# Project_PCBTA.net
KiCad netlist of a schematic drawn in Altium Designer
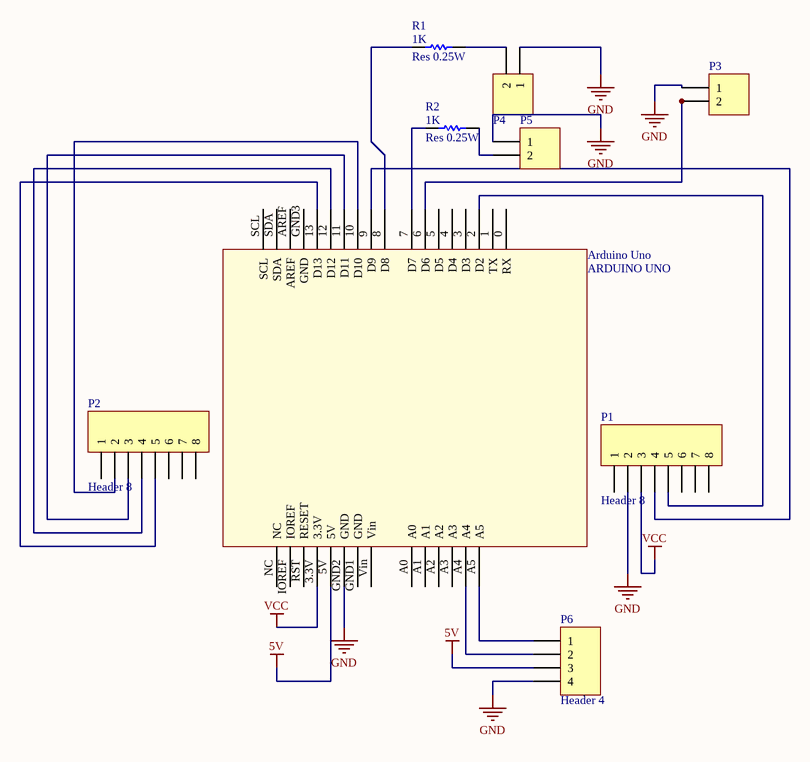
[diagram p0: Project_PCBTA.SchDoc]

(export (version "E")
  (design (tool "Eeschema 10.0.6"))
  (components
    (comp (ref "Arduino Uno")
      (value "ARDUINO UNO")
      (footprint "ARDUINO UNO")
      (libsource (lib "Arduino") (part "ARDUINO UNO"))
    )
    (comp (ref "P1")
      (value "Header 8")
      (footprint "HDR1X8")
      (description "Header, 8-Pin")
      (fields (field (name "PUBLISHER") "Altium Limited"))
      (libsource (lib "Miscellaneous Connectors") (part "Header 8"))
    )
    (comp (ref "P2")
      (value "Header 8")
      (footprint "HDR1X8")
      (description "Header, 8-Pin")
      (fields (field (name "PUBLISHER") "Altium Limited"))
      (libsource (lib "Miscellaneous Connectors") (part "Header 8"))
    )
    (comp (ref "P3")
      (value "Header 2")
      (footprint "My_1X02")
      (description "Header, 2-Pin")
      (fields (field (name "PUBLISHER") "Altium Limited"))
      (libsource (lib "Mylib") (part "Header 2"))
    )
    (comp (ref "P4")
      (value "Header 2")
      (footprint "My_1X02")
      (description "Header, 2-Pin")
      (fields (field (name "PUBLISHER") "Altium Limited"))
      (libsource (lib "") (part "Header 2_1"))
    )
    (comp (ref "P5")
      (value "Header 2")
      (footprint "My_1X02")
      (description "Header, 2-Pin")
      (fields (field (name "PUBLISHER") "Altium Limited"))
      (libsource (lib "Mylib") (part "Header 2"))
    )
    (comp (ref "P6")
      (value "Header 4")
      (footprint "HDR1X4")
      (description "Header, 4-Pin")
      (fields (field (name "PUBLISHER") "Altium Limited"))
      (libsource (lib "Miscellaneous Connectors") (part "Header 4"))
    )
    (comp (ref "R1")
      (value "Res 0.25W")
      (footprint "Res 0.25")
      (libsource (lib "Error15 Library REV") (part "Res 0.25W"))
    )
    (comp (ref "R2")
      (value "Res 0.25W")
      (footprint "Res 0.25")
      (libsource (lib "Error15 Library REV") (part "Res 0.25W"))
    )
  )
  (nets
    (net (code "1") (name "5V") (class "Default")
      (node (ref "Arduino Uno") (pin "5V") (pinfunction "5V_5V") (pintype "passive"))
      (node (ref "P6") (pin "3") (pinfunction "3_3") (pintype "passive"))
    )
    (net (code "2") (name "GND") (class "Default")
      (node (ref "Arduino Uno") (pin "GND2") (pinfunction "GND_GND2") (pintype "passive"))
      (node (ref "P1") (pin "2") (pinfunction "2_2") (pintype "passive"))
      (node (ref "P3") (pin "1") (pinfunction "1_1") (pintype "passive"))
      (node (ref "P4") (pin "1") (pinfunction "1_1") (pintype "passive"))
      (node (ref "P5") (pin "1") (pinfunction "1_1") (pintype "passive"))
      (node (ref "P6") (pin "4") (pinfunction "4_4") (pintype "passive"))
    )
    (net (code "3") (name "Net-(Arduino Uno-D2)") (class "Default")
      (node (ref "Arduino Uno") (pin "2") (pinfunction "D2_2") (pintype "passive"))
      (node (ref "P1") (pin "5") (pinfunction "5_5") (pintype "passive"))
    )
    (net (code "4") (name "Net-(Arduino Uno-D6)") (class "Default")
      (node (ref "Arduino Uno") (pin "6") (pinfunction "D6_6") (pintype "passive"))
      (node (ref "P3") (pin "2") (pinfunction "2_2") (pintype "passive"))
    )
    (net (code "5") (name "Net-(Arduino Uno-D7)") (class "Default")
      (node (ref "Arduino Uno") (pin "7") (pinfunction "D7_7") (pintype "passive"))
      (node (ref "R2") (pin "1") (pinfunction "1_1") (pintype "passive"))
    )
    (net (code "6") (name "Net-(Arduino Uno-D8)") (class "Default")
      (node (ref "Arduino Uno") (pin "8") (pinfunction "D8_8") (pintype "passive"))
      (node (ref "R1") (pin "1") (pinfunction "1_1") (pintype "passive"))
    )
    (net (code "7") (name "Net-(Arduino Uno-D9)") (class "Default")
      (node (ref "Arduino Uno") (pin "9") (pinfunction "D9_9") (pintype "passive"))
      (node (ref "P1") (pin "4") (pinfunction "4_4") (pintype "passive"))
    )
    (net (code "8") (name "Net-(Arduino Uno-D10)") (class "Default")
      (node (ref "Arduino Uno") (pin "10") (pinfunction "D10_10") (pintype "passive"))
      (node (ref "P2") (pin "2") (pinfunction "2_2") (pintype "passive"))
    )
    (net (code "9") (name "Net-(Arduino Uno-D11)") (class "Default")
      (node (ref "Arduino Uno") (pin "11") (pinfunction "D11_11") (pintype "passive"))
      (node (ref "P2") (pin "3") (pinfunction "3_3") (pintype "passive"))
    )
    (net (code "10") (name "Net-(Arduino Uno-D12)") (class "Default")
      (node (ref "Arduino Uno") (pin "12") (pinfunction "D12_12") (pintype "passive"))
      (node (ref "P2") (pin "4") (pinfunction "4_4") (pintype "passive"))
    )
    (net (code "11") (name "Net-(Arduino Uno-D13)") (class "Default")
      (node (ref "Arduino Uno") (pin "13") (pinfunction "D13_13") (pintype "passive"))
      (node (ref "P2") (pin "5") (pinfunction "5_5") (pintype "passive"))
    )
    (net (code "12") (name "Net-(Arduino Uno-PadA4)") (class "Default")
      (node (ref "Arduino Uno") (pin "A4") (pinfunction "A4_A4") (pintype "passive"))
      (node (ref "P6") (pin "2") (pinfunction "2_2") (pintype "passive"))
    )
    (net (code "13") (name "Net-(Arduino Uno-PadA5)") (class "Default")
      (node (ref "Arduino Uno") (pin "A5") (pinfunction "A5_A5") (pintype "passive"))
      (node (ref "P6") (pin "1") (pinfunction "1_1") (pintype "passive"))
    )
    (net (code "14") (name "Net-(P4-Pad2)") (class "Default")
      (node (ref "P4") (pin "2") (pinfunction "2_2") (pintype "passive"))
      (node (ref "R1") (pin "2") (pinfunction "2_2") (pintype "passive"))
    )
    (net (code "15") (name "Net-(P5-Pad2)") (class "Default")
      (node (ref "P5") (pin "2") (pinfunction "2_2") (pintype "passive"))
      (node (ref "R2") (pin "2") (pinfunction "2_2") (pintype "passive"))
    )
    (net (code "16") (name "VCC") (class "Default")
      (node (ref "Arduino Uno") (pin "3.3V") (pinfunction "3.3V_3.3V") (pintype "passive"))
      (node (ref "P1") (pin "3") (pinfunction "3_3") (pintype "passive"))
    )
    (net (code "17") (name "unconnected-(Arduino Uno-D3-Pad3)") (class "Default")
      (node (ref "Arduino Uno") (pin "3") (pinfunction "D3_3") (pintype "passive"))
    )
    (net (code "18") (name "unconnected-(Arduino Uno-D4-Pad4)") (class "Default")
      (node (ref "Arduino Uno") (pin "4") (pinfunction "D4_4") (pintype "passive"))
    )
    (net (code "19") (name "unconnected-(Arduino Uno-D5-Pad5)") (class "Default")
      (node (ref "Arduino Uno") (pin "5") (pinfunction "D5_5") (pintype "passive"))
    )
    (net (code "20") (name "unconnected-(Arduino Uno-GND-PadGND1)") (class "Default")
      (node (ref "Arduino Uno") (pin "GND1") (pinfunction "GND_GND1") (pintype "passive"))
    )
    (net (code "21") (name "unconnected-(Arduino Uno-GND-PadGND3)") (class "Default")
      (node (ref "Arduino Uno") (pin "GND3") (pinfunction "GND_GND3") (pintype "passive"))
    )
    (net (code "22") (name "unconnected-(Arduino Uno-PadA0)") (class "Default")
      (node (ref "Arduino Uno") (pin "A0") (pinfunction "A0_A0") (pintype "passive"))
    )
    (net (code "23") (name "unconnected-(Arduino Uno-PadA1)") (class "Default")
      (node (ref "Arduino Uno") (pin "A1") (pinfunction "A1_A1") (pintype "passive"))
    )
    (net (code "24") (name "unconnected-(Arduino Uno-PadA2)") (class "Default")
      (node (ref "Arduino Uno") (pin "A2") (pinfunction "A2_A2") (pintype "passive"))
    )
    (net (code "25") (name "unconnected-(Arduino Uno-PadA3)") (class "Default")
      (node (ref "Arduino Uno") (pin "A3") (pinfunction "A3_A3") (pintype "passive"))
    )
    (net (code "26") (name "unconnected-(Arduino Uno-PadAREF)") (class "Default")
      (node (ref "Arduino Uno") (pin "AREF") (pinfunction "AREF_AREF") (pintype "passive"))
    )
    (net (code "27") (name "unconnected-(Arduino Uno-PadIOREF)") (class "Default")
      (node (ref "Arduino Uno") (pin "IOREF") (pinfunction "IOREF_IOREF") (pintype "passive"))
    )
    (net (code "28") (name "unconnected-(Arduino Uno-PadNC)") (class "Default")
      (node (ref "Arduino Uno") (pin "NC") (pinfunction "NC_NC") (pintype "passive"))
    )
    (net (code "29") (name "unconnected-(Arduino Uno-PadSCL)") (class "Default")
      (node (ref "Arduino Uno") (pin "SCL") (pinfunction "SCL_SCL") (pintype "passive"))
    )
    (net (code "30") (name "unconnected-(Arduino Uno-PadSDA)") (class "Default")
      (node (ref "Arduino Uno") (pin "SDA") (pinfunction "SDA_SDA") (pintype "passive"))
    )
    (net (code "31") (name "unconnected-(Arduino Uno-PadVin)") (class "Default")
      (node (ref "Arduino Uno") (pin "Vin") (pinfunction "Vin_Vin") (pintype "passive"))
    )
    (net (code "32") (name "unconnected-(Arduino Uno-RESET-PadRST)") (class "Default")
      (node (ref "Arduino Uno") (pin "RST") (pinfunction "RESET_RST") (pintype "passive"))
    )
    (net (code "33") (name "unconnected-(Arduino Uno-RX-Pad0)") (class "Default")
      (node (ref "Arduino Uno") (pin "0") (pinfunction "RX_0") (pintype "passive"))
    )
    (net (code "34") (name "unconnected-(Arduino Uno-TX-Pad1)") (class "Default")
      (node (ref "Arduino Uno") (pin "1") (pinfunction "TX_1") (pintype "passive"))
    )
    (net (code "35") (name "unconnected-(P1-Pad1)") (class "Default")
      (node (ref "P1") (pin "1") (pinfunction "1_1") (pintype "passive"))
    )
    (net (code "36") (name "unconnected-(P1-Pad6)") (class "Default")
      (node (ref "P1") (pin "6") (pinfunction "6_6") (pintype "passive"))
    )
    (net (code "37") (name "unconnected-(P1-Pad7)") (class "Default")
      (node (ref "P1") (pin "7") (pinfunction "7_7") (pintype "passive"))
    )
    (net (code "38") (name "unconnected-(P1-Pad8)") (class "Default")
      (node (ref "P1") (pin "8") (pinfunction "8_8") (pintype "passive"))
    )
    (net (code "39") (name "unconnected-(P2-Pad1)") (class "Default")
      (node (ref "P2") (pin "1") (pinfunction "1_1") (pintype "passive"))
    )
    (net (code "40") (name "unconnected-(P2-Pad6)") (class "Default")
      (node (ref "P2") (pin "6") (pinfunction "6_6") (pintype "passive"))
    )
    (net (code "41") (name "unconnected-(P2-Pad7)") (class "Default")
      (node (ref "P2") (pin "7") (pinfunction "7_7") (pintype "passive"))
    )
    (net (code "42") (name "unconnected-(P2-Pad8)") (class "Default")
      (node (ref "P2") (pin "8") (pinfunction "8_8") (pintype "passive"))
    )
  )
)
